# RS232.net
KiCad netlist of a schematic drawn in Altium Designer
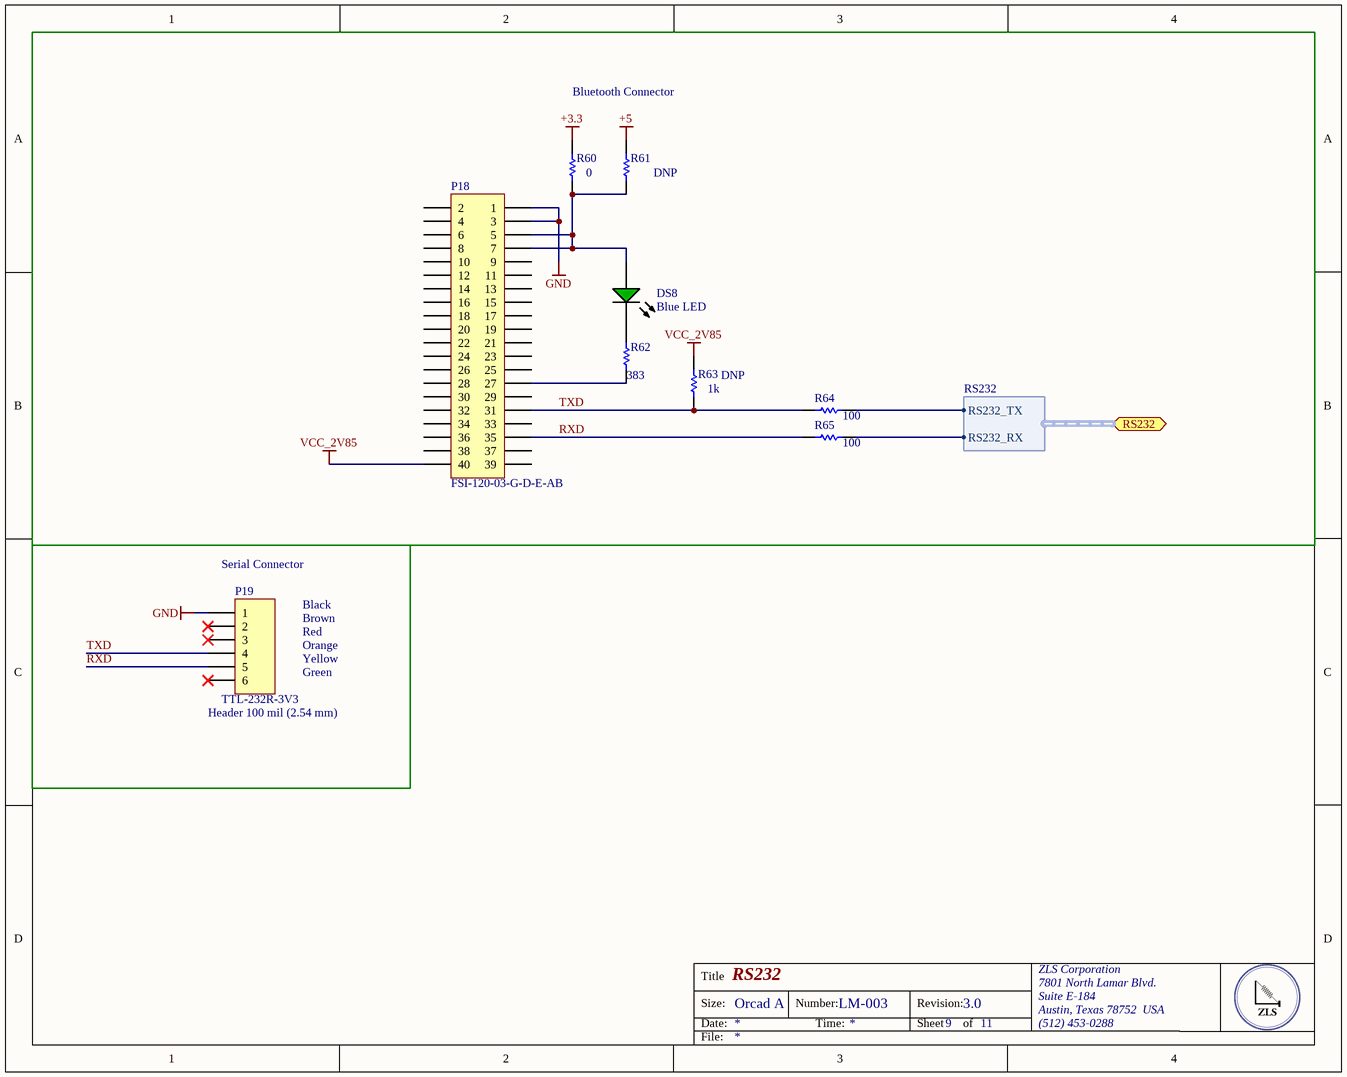
[diagram p0: RS232.SchDoc]

(export (version "E")
  (design (tool "Eeschema 10.0.6"))
  (components
    (comp (ref "DS8")
      (value "Blue LED")
      (footprint "KING-LED0603-25-GREEN_V")
      (description "LED 468NM BLUE CLEAR 0603 SMD")
      (libsource (lib "Altium Content Vault") (part "CMP-0239-00001-1"))
    )
    (comp (ref "P18")
      (value "FSI-120-03-G-D-E-AB")
      (footprint "FSI-120-03-G-D-E-AB")
      (description "1MM SINGLE ELEMENT INTERFACE")
      (libsource (lib "Miscellaneous Connectors") (part "Header 20X2"))
    )
    (comp (ref "P19")
      (value "Header 100 mil (2.54 mm)")
      (footprint "HDR1X6")
      (description "CABLE USB SERIAL 3.3V 2MM HEADER")
      (libsource (lib "Miscellaneous Connectors") (part "Header 6H"))
    )
    (comp (ref "R60")
      (value "RES SMD 0.0 OHM JUMPER 1/8W 0805")
      (footprint "RESC0805(2012)_M")
      (fields
        (field (name "MANUFACTURER") "Vishay")
        (field (name "MANUFACTURER PART NUMBER") "CRCW08050000Z0EA")
        (field (name "RESISTANCE") "0")
        (field (name "TOLERANCE") "1%")
      )
      (libsource (lib "Altium Content Vault") (part "CMP-1013-00017-1"))
    )
    (comp (ref "R61")
      (value "DNP")
      (footprint "RESC0805(2012)_M")
      (description "RES SMD 0.0 OHM JUMPER 1/8W 0805")
      (fields
        (field (name "MANUFACTURER") "Vishay")
        (field (name "MANUFACTURER PART NUMBER") "CRCW08050000Z0EA")
      )
      (libsource (lib "Altium Content Vault") (part "CMP-1013-00017-1"))
    )
    (comp (ref "R62")
      (value "RES SMD 383 OHM 1% 1/8W 0805")
      (footprint "RESC0805(2012)_M")
      (fields
        (field (name "MANUFACTURER") "Vishay Dale")
        (field (name "MANUFACTURER PART NUMBER") "CRCW0805383RFKEA")
        (field (name "RESISTANCE (OHMS)") "383")
        (field (name "TOLERANCE") "±1%")
      )
      (libsource (lib "Altium Content Vault") (part "CMP-1013-00017-1"))
    )
    (comp (ref "R63")
      (value "DNP")
      (footprint "RESC0805(2012)_M")
      (description "RES SMD 1K OHM 1% 1/2W 0805")
      (fields
        (field (name "MANUFACTURER") "Vishay Dale")
        (field (name "MANUFACTURER PART NUMBER") "CRCW08051K00FKEAHP")
        (field (name "RESISTANCE (OHMS)") "1k")
      )
      (libsource (lib "Altium Content Vault") (part "CMP-1013-00017-1"))
    )
    (comp (ref "R64")
      (value "RES SMD 100 OHM 1% 1/8W 0805")
      (footprint "RESC0805(2012)_L")
      (fields
        (field (name "MANUFACTURER") "Vishay Dale")
        (field (name "MANUFACTURER PART NUMBER") "CRCW0805100RFKEA")
        (field (name "RESISTANCE (OHMS)") "100")
        (field (name "TOLERANCE") "±1%")
      )
      (libsource (lib "Altium Content Vault") (part "CMP-1013-00393-1"))
    )
    (comp (ref "R65")
      (value "RES SMD 100 OHM 1% 1/8W 0805")
      (footprint "RESC0805(2012)_N")
      (fields
        (field (name "MANUFACTURER") "Vishay Dale")
        (field (name "MANUFACTURER PART NUMBER") "CRCW0805100RFKEA")
        (field (name "RESISTANCE (OHMS)") "100")
        (field (name "TOLERANCE") "±1%")
      )
      (libsource (lib "Altium Content Vault") (part "CMP-1013-00393-1"))
    )
  )
  (nets
    (net (code "2") (name "+3.3") (class "Default")
      (node (ref "R60") (pin "2") (pinfunction "2_2") (pintype "passive"))
    )
    (net (code "3") (name "+5") (class "Default")
      (node (ref "R61") (pin "2") (pinfunction "2_2") (pintype "passive"))
    )
    (net (code "4") (name "/RS232_RX") (class "Default")
      (node (ref "R65") (pin "1") (pinfunction "1_1") (pintype "passive"))
    )
    (net (code "5") (name "/RS232_TX") (class "Default")
      (node (ref "R64") (pin "1") (pinfunction "1_1") (pintype "passive"))
    )
    (net (code "6") (name "/RXD") (class "Default")
      (node (ref "P18") (pin "35") (pinfunction "35_35") (pintype "passive"))
      (node (ref "P19") (pin "5") (pinfunction "5_5") (pintype "passive"))
      (node (ref "R65") (pin "2") (pinfunction "2_2") (pintype "passive"))
    )
    (net (code "7") (name "/TXD") (class "Default")
      (node (ref "P18") (pin "31") (pinfunction "31_31") (pintype "passive"))
      (node (ref "P19") (pin "4") (pinfunction "4_4") (pintype "passive"))
      (node (ref "R63") (pin "1") (pinfunction "1_1") (pintype "passive"))
      (node (ref "R64") (pin "2") (pinfunction "2_2") (pintype "passive"))
    )
    (net (code "9") (name "GND") (class "Default")
      (node (ref "P18") (pin "1") (pinfunction "1_1") (pintype "passive"))
      (node (ref "P18") (pin "3") (pinfunction "3_3") (pintype "passive"))
      (node (ref "P19") (pin "1") (pinfunction "1_1") (pintype "passive"))
    )
    (net (code "10") (name "Net-(DS8-A)") (class "Default")
      (node (ref "DS8") (pin "1") (pinfunction "A_1") (pintype "passive"))
      (node (ref "P18") (pin "5") (pinfunction "5_5") (pintype "passive"))
      (node (ref "P18") (pin "7") (pinfunction "7_7") (pintype "passive"))
      (node (ref "R60") (pin "1") (pinfunction "1_1") (pintype "passive"))
      (node (ref "R61") (pin "1") (pinfunction "1_1") (pintype "passive"))
    )
    (net (code "11") (name "Net-(DS8-K)") (class "Default")
      (node (ref "DS8") (pin "2") (pinfunction "K_2") (pintype "passive"))
      (node (ref "R62") (pin "2") (pinfunction "2_2") (pintype "passive"))
    )
    (net (code "12") (name "Net-(P18-Pad27)") (class "Default")
      (node (ref "P18") (pin "27") (pinfunction "27_27") (pintype "passive"))
      (node (ref "R62") (pin "1") (pinfunction "1_1") (pintype "passive"))
    )
    (net (code "13") (name "VCC_2V85") (class "Default")
      (node (ref "P18") (pin "40") (pinfunction "40_40") (pintype "passive"))
      (node (ref "R63") (pin "2") (pinfunction "2_2") (pintype "passive"))
    )
    (net (code "14") (name "unconnected-(P18-Pad2)") (class "Default")
      (node (ref "P18") (pin "2") (pinfunction "2_2") (pintype "passive"))
    )
    (net (code "15") (name "unconnected-(P18-Pad4)") (class "Default")
      (node (ref "P18") (pin "4") (pinfunction "4_4") (pintype "passive"))
    )
    (net (code "16") (name "unconnected-(P18-Pad6)") (class "Default")
      (node (ref "P18") (pin "6") (pinfunction "6_6") (pintype "passive"))
    )
    (net (code "17") (name "unconnected-(P18-Pad8)") (class "Default")
      (node (ref "P18") (pin "8") (pinfunction "8_8") (pintype "passive"))
    )
    (net (code "18") (name "unconnected-(P18-Pad9)") (class "Default")
      (node (ref "P18") (pin "9") (pinfunction "9_9") (pintype "passive"))
    )
    (net (code "19") (name "unconnected-(P18-Pad10)") (class "Default")
      (node (ref "P18") (pin "10") (pinfunction "10_10") (pintype "passive"))
    )
    (net (code "20") (name "unconnected-(P18-Pad11)") (class "Default")
      (node (ref "P18") (pin "11") (pinfunction "11_11") (pintype "passive"))
    )
    (net (code "21") (name "unconnected-(P18-Pad12)") (class "Default")
      (node (ref "P18") (pin "12") (pinfunction "12_12") (pintype "passive"))
    )
    (net (code "22") (name "unconnected-(P18-Pad13)") (class "Default")
      (node (ref "P18") (pin "13") (pinfunction "13_13") (pintype "passive"))
    )
    (net (code "23") (name "unconnected-(P18-Pad14)") (class "Default")
      (node (ref "P18") (pin "14") (pinfunction "14_14") (pintype "passive"))
    )
    (net (code "24") (name "unconnected-(P18-Pad15)") (class "Default")
      (node (ref "P18") (pin "15") (pinfunction "15_15") (pintype "passive"))
    )
    (net (code "25") (name "unconnected-(P18-Pad16)") (class "Default")
      (node (ref "P18") (pin "16") (pinfunction "16_16") (pintype "passive"))
    )
    (net (code "26") (name "unconnected-(P18-Pad17)") (class "Default")
      (node (ref "P18") (pin "17") (pinfunction "17_17") (pintype "passive"))
    )
    (net (code "27") (name "unconnected-(P18-Pad18)") (class "Default")
      (node (ref "P18") (pin "18") (pinfunction "18_18") (pintype "passive"))
    )
    (net (code "28") (name "unconnected-(P18-Pad19)") (class "Default")
      (node (ref "P18") (pin "19") (pinfunction "19_19") (pintype "passive"))
    )
    (net (code "29") (name "unconnected-(P18-Pad20)") (class "Default")
      (node (ref "P18") (pin "20") (pinfunction "20_20") (pintype "passive"))
    )
    (net (code "30") (name "unconnected-(P18-Pad21)") (class "Default")
      (node (ref "P18") (pin "21") (pinfunction "21_21") (pintype "passive"))
    )
    (net (code "31") (name "unconnected-(P18-Pad22)") (class "Default")
      (node (ref "P18") (pin "22") (pinfunction "22_22") (pintype "passive"))
    )
    (net (code "32") (name "unconnected-(P18-Pad23)") (class "Default")
      (node (ref "P18") (pin "23") (pinfunction "23_23") (pintype "passive"))
    )
    (net (code "33") (name "unconnected-(P18-Pad24)") (class "Default")
      (node (ref "P18") (pin "24") (pinfunction "24_24") (pintype "passive"))
    )
    (net (code "34") (name "unconnected-(P18-Pad25)") (class "Default")
      (node (ref "P18") (pin "25") (pinfunction "25_25") (pintype "passive"))
    )
    (net (code "35") (name "unconnected-(P18-Pad26)") (class "Default")
      (node (ref "P18") (pin "26") (pinfunction "26_26") (pintype "passive"))
    )
    (net (code "36") (name "unconnected-(P18-Pad28)") (class "Default")
      (node (ref "P18") (pin "28") (pinfunction "28_28") (pintype "passive"))
    )
    (net (code "37") (name "unconnected-(P18-Pad29)") (class "Default")
      (node (ref "P18") (pin "29") (pinfunction "29_29") (pintype "passive"))
    )
    (net (code "38") (name "unconnected-(P18-Pad30)") (class "Default")
      (node (ref "P18") (pin "30") (pinfunction "30_30") (pintype "passive"))
    )
    (net (code "39") (name "unconnected-(P18-Pad32)") (class "Default")
      (node (ref "P18") (pin "32") (pinfunction "32_32") (pintype "passive"))
    )
    (net (code "40") (name "unconnected-(P18-Pad33)") (class "Default")
      (node (ref "P18") (pin "33") (pinfunction "33_33") (pintype "passive"))
    )
    (net (code "41") (name "unconnected-(P18-Pad34)") (class "Default")
      (node (ref "P18") (pin "34") (pinfunction "34_34") (pintype "passive"))
    )
    (net (code "42") (name "unconnected-(P18-Pad36)") (class "Default")
      (node (ref "P18") (pin "36") (pinfunction "36_36") (pintype "passive"))
    )
    (net (code "43") (name "unconnected-(P18-Pad37)") (class "Default")
      (node (ref "P18") (pin "37") (pinfunction "37_37") (pintype "passive"))
    )
    (net (code "44") (name "unconnected-(P18-Pad38)") (class "Default")
      (node (ref "P18") (pin "38") (pinfunction "38_38") (pintype "passive"))
    )
    (net (code "45") (name "unconnected-(P18-Pad39)") (class "Default")
      (node (ref "P18") (pin "39") (pinfunction "39_39") (pintype "passive"))
    )
    (net (code "46") (name "unconnected-(P19-Pad2)") (class "Default")
      (node (ref "P19") (pin "2") (pinfunction "2_2") (pintype "passive+no_connect"))
    )
    (net (code "47") (name "unconnected-(P19-Pad3)") (class "Default")
      (node (ref "P19") (pin "3") (pinfunction "3_3") (pintype "passive+no_connect"))
    )
    (net (code "48") (name "unconnected-(P19-Pad6)") (class "Default")
      (node (ref "P19") (pin "6") (pinfunction "6_6") (pintype "passive+no_connect"))
    )
  )
)
